# digital_host_for_ADS1216_main.net
KiCad netlist of a schematic drawn in Altium Designer
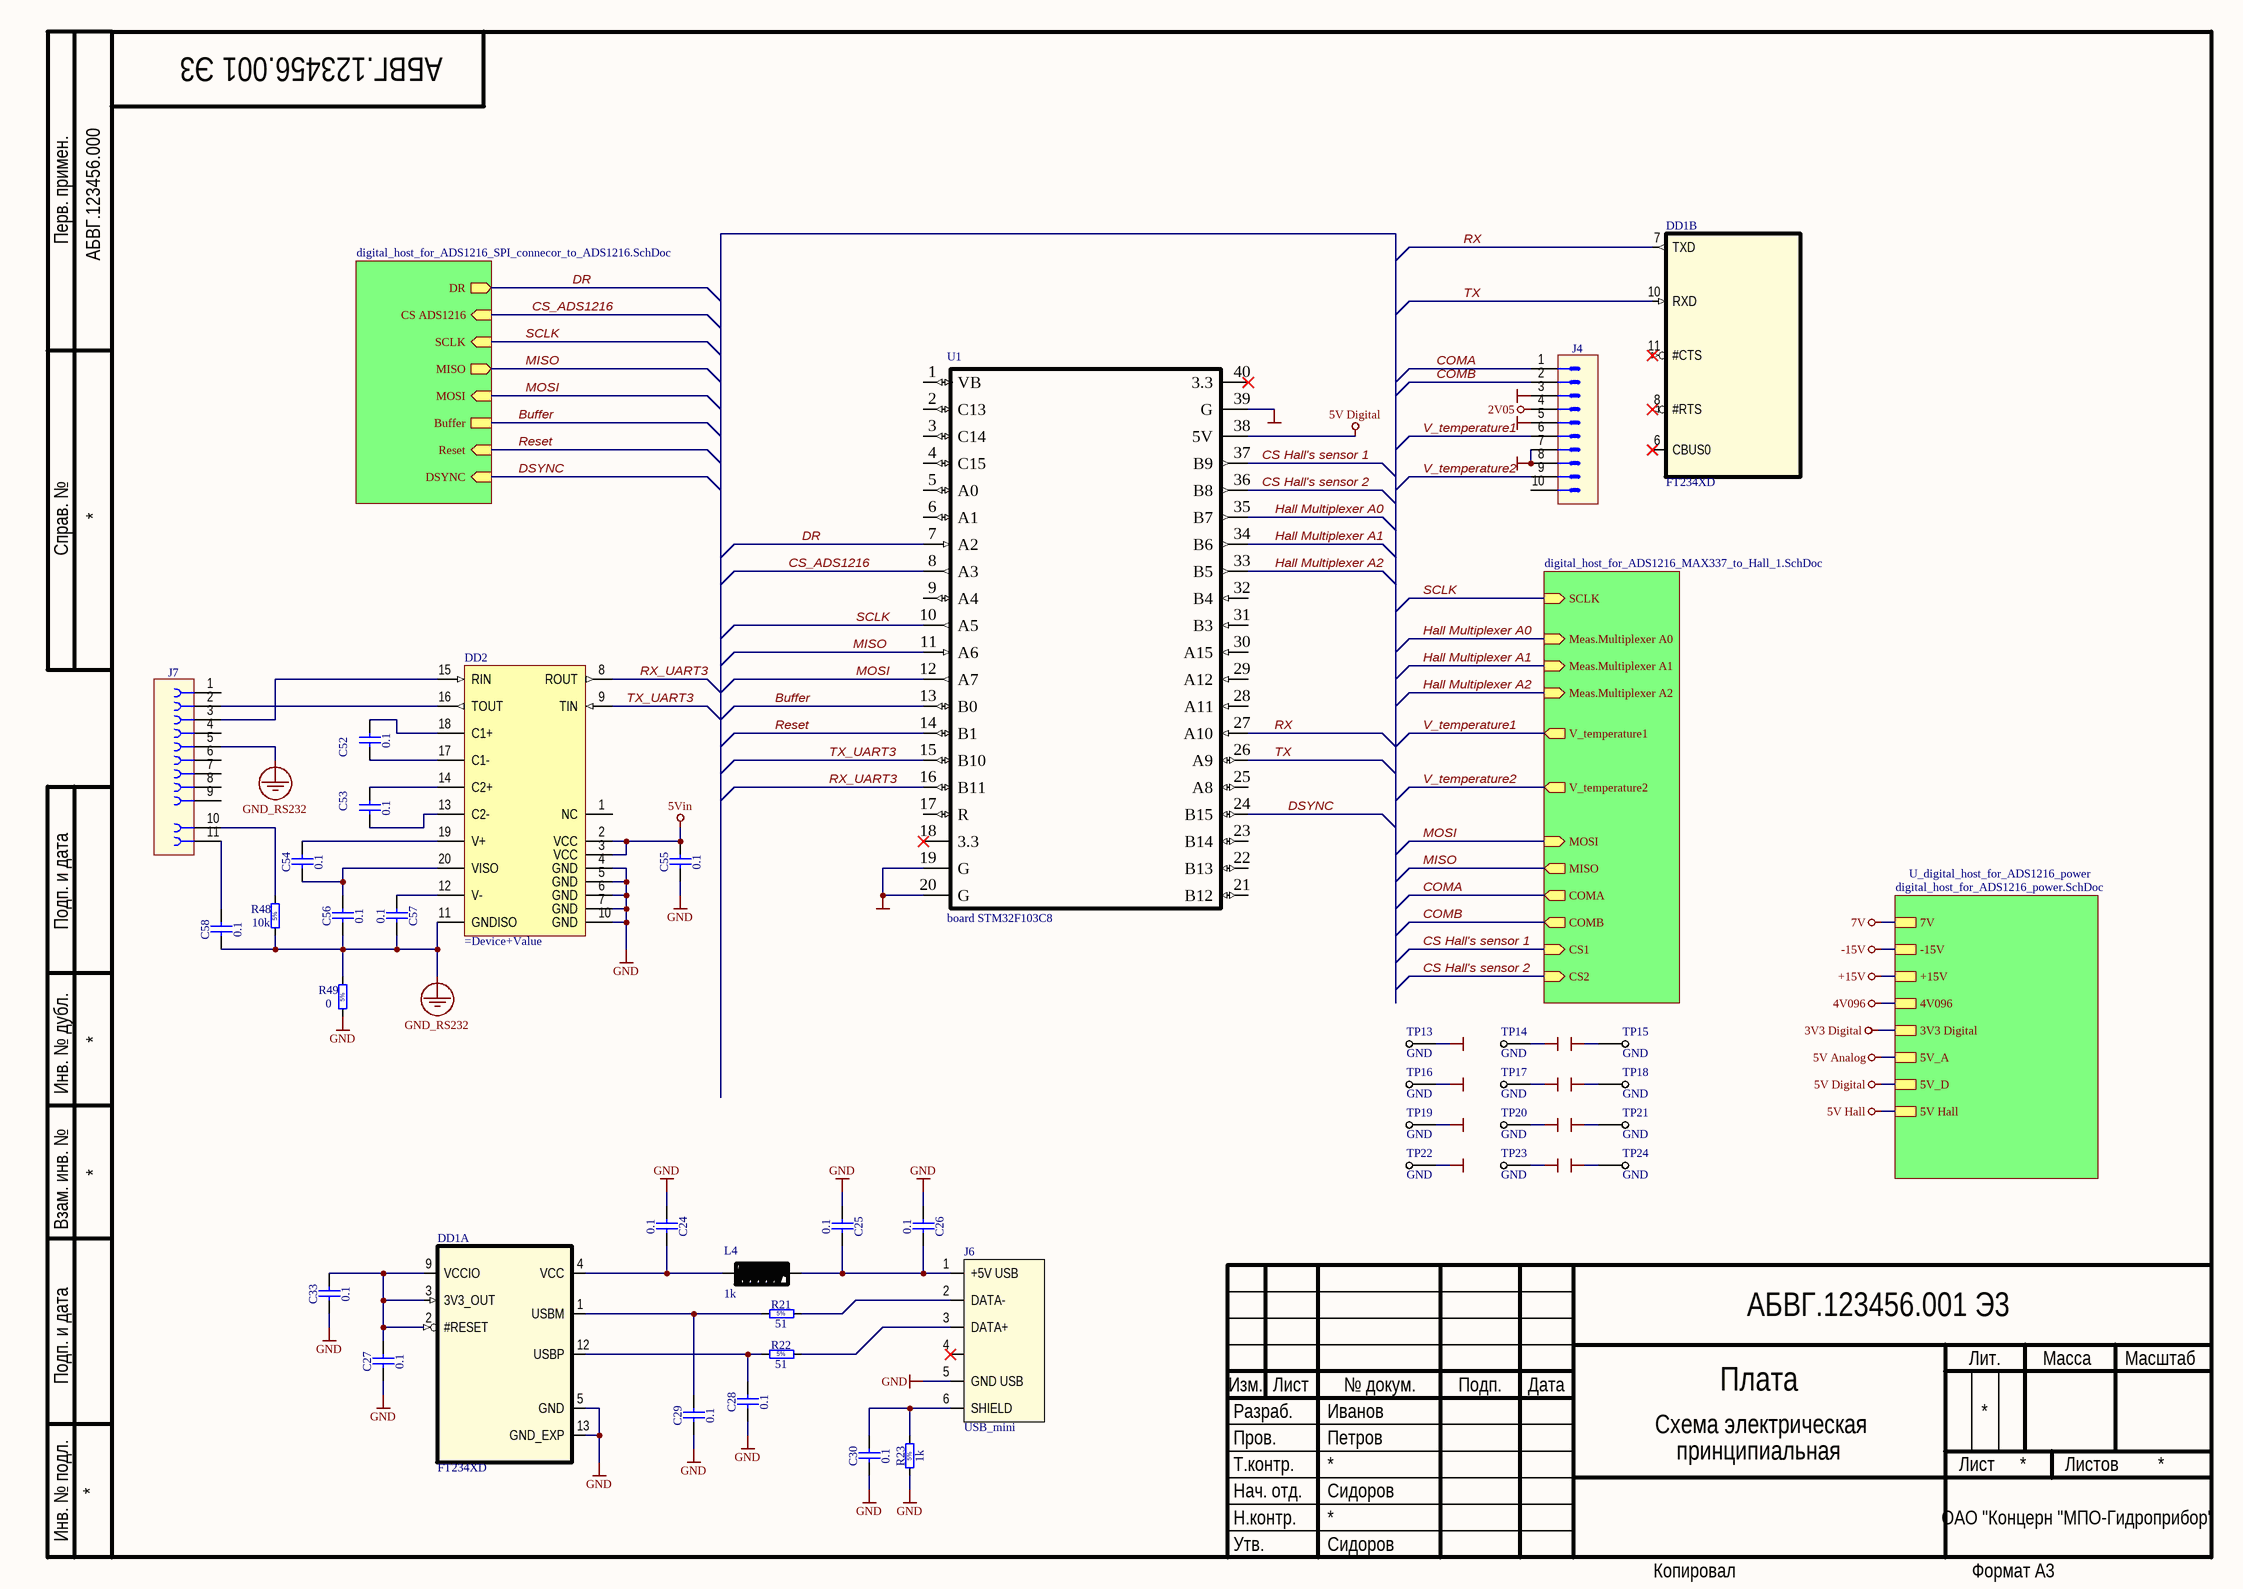
[diagram p0: digital_host_for_ADS1216_main.SchDoc]

(export (version "E")
  (design (tool "Eeschema 10.0.6"))
  (components
    (comp (ref "C24")
      (value "0.1")
      (footprint "CAPC2012X90N")
      (description "Non-polarised capacitor2012")
      (libsource (lib "schematic_hall_library") (part "Capacitor - non polarized"))
    )
    (comp (ref "C25")
      (value "0.1")
      (footprint "CAPC2012X90N")
      (description "Non-polarised capacitor2012")
      (libsource (lib "schematic_hall_library") (part "Capacitor - non polarized"))
    )
    (comp (ref "C26")
      (value "0.1")
      (footprint "CAPC2012X90N")
      (description "Non-polarised capacitor2012")
      (libsource (lib "schematic_hall_library") (part "Capacitor - non polarized"))
    )
    (comp (ref "C27")
      (value "0.1")
      (footprint "CAPC2012X90N")
      (description "Non-polarised capacitor2012")
      (libsource (lib "schematic_hall_library") (part "Capacitor - non polarized"))
    )
    (comp (ref "C28")
      (value "0.1")
      (footprint "CAPC2012X90N")
      (description "Non-polarised capacitor2012")
      (libsource (lib "schematic_hall_library") (part "Capacitor - non polarized"))
    )
    (comp (ref "C29")
      (value "0.1")
      (footprint "CAPC2012X90N")
      (description "Non-polarised capacitor2012")
      (libsource (lib "schematic_hall_library") (part "Capacitor - non polarized"))
    )
    (comp (ref "C30")
      (value "0.1")
      (footprint "CAPC2012X90N")
      (description "Non-polarised capacitor2012")
      (libsource (lib "schematic_hall_library") (part "Capacitor - non polarized"))
    )
    (comp (ref "C33")
      (value "0.1")
      (footprint "CAPC2012X90N")
      (description "Non-polarised capacitor2012")
      (libsource (lib "schematic_hall_library") (part "Capacitor - non polarized"))
    )
    (comp (ref "C52")
      (value "0.1")
      (footprint "CAPC2012X90N")
      (description "Non-polarised capacitor2012")
      (libsource (lib "schematic_hall_library") (part "Capacitor - non polarized"))
    )
    (comp (ref "C53")
      (value "0.1")
      (footprint "CAPC2012X90N")
      (description "Non-polarised capacitor2012")
      (libsource (lib "schematic_hall_library") (part "Capacitor - non polarized"))
    )
    (comp (ref "C54")
      (value "0.1")
      (footprint "CAPC2012X90N")
      (description "Non-polarised capacitor2012")
      (libsource (lib "schematic_hall_library") (part "Capacitor - non polarized"))
    )
    (comp (ref "C55")
      (value "0.1")
      (footprint "CAPC2012X90N")
      (description "Non-polarised capacitor2012")
      (libsource (lib "schematic_hall_library") (part "Capacitor - non polarized"))
    )
    (comp (ref "C56")
      (value "0.1")
      (footprint "CAPC2012X90N")
      (description "Non-polarised capacitor2012")
      (libsource (lib "schematic_hall_library") (part "Capacitor - non polarized"))
    )
    (comp (ref "C57")
      (value "0.1")
      (footprint "CAPC2012X90N")
      (description "Non-polarised capacitor2012")
      (libsource (lib "schematic_hall_library") (part "Capacitor - non polarized"))
    )
    (comp (ref "C58")
      (value "0.1")
      (footprint "CAPC2012X90N")
      (description "Non-polarised capacitor2012")
      (libsource (lib "schematic_hall_library") (part "Capacitor - non polarized"))
    )
    (comp (ref "DD1")
      (value "FT234XD")
      (footprint "DFN_12-045")
      (description "USB-UART driver")
      (libsource (lib "") (part "FT234XD_1"))
    )
    (comp (ref "DD2")
      (value "ADM3251")
      (footprint "footprint_hall_library:SOIC127P1032X265-20N")
      (description "Driver UART-RS232")
      (libsource (lib "schematic_hall_library") (part "ADM3251"))
    )
    (comp (ref "J4")
      (value "~")
      (footprint "footprint_library:3M_N2510-6002RB")
      (description "Connector 10 Male")
      (libsource (lib "first_scheme.~(65)") (part "Connector 10 Male"))
    )
    (comp (ref "J6")
      (value "USB_mini")
      (footprint "TYCO_1734035-1")
      (description "Вилка  PLS 6x2.54")
      (libsource (lib "Integrated_Library1") (part "USB_mini"))
    )
    (comp (ref "J7")
      (value "~")
      (footprint "footprint_hall_library:TYCO_5747844-5")
      (description "Connector 9 Female")
      (libsource (lib "schematic_hall_library") (part "Connector 9 Female"))
    )
    (comp (ref "L4")
      (value "1k")
      (footprint "footprint_library:RESC2012X50N")
      (description "SMD Ferrite bead 0805")
      (libsource (lib "first_scheme.~(65)") (part "BLM21"))
    )
    (comp (ref "R21")
      (value "51")
      (footprint "RESC2012X70N")
      (description "Resistor - 5%")
      (fields (field (name "TOLERANCE") "5%"))
      (libsource (lib "first_scheme.~(65)") (part "Resistor - 5%"))
    )
    (comp (ref "R22")
      (value "51")
      (footprint "RESC2012X70N")
      (description "Resistor - 5%")
      (fields (field (name "TOLERANCE") "5%"))
      (libsource (lib "first_scheme.~(65)") (part "Resistor - 5%"))
    )
    (comp (ref "R23")
      (value "1k")
      (footprint "RESC2012X70N")
      (description "Resistor - 5%")
      (fields (field (name "TOLERANCE") "5%"))
      (libsource (lib "first_scheme.~(65)") (part "Resistor - 5%"))
    )
    (comp (ref "R48")
      (value "10k")
      (footprint "RESC2012X70N")
      (description "Resistor - 5%")
      (fields (field (name "TOLERANCE") "5%"))
      (libsource (lib "first_scheme.~(65)") (part "Resistor - 5%"))
    )
    (comp (ref "R49")
      (value "0")
      (footprint "RESC2012X70N")
      (description "Resistor - 5%")
      (fields (field (name "TOLERANCE") "5%"))
      (libsource (lib "first_scheme.~(65)") (part "Resistor - 5%"))
    )
    (comp (ref "TP13")
      (value "GND")
      (footprint "TP1")
      (description "Контрольная точка")
      (libsource (lib "Integrated_Library1") (part "TP"))
    )
    (comp (ref "TP14")
      (value "GND")
      (footprint "TP1")
      (description "Контрольная точка")
      (libsource (lib "Integrated_Library1") (part "TP"))
    )
    (comp (ref "TP15")
      (value "GND")
      (footprint "TP1")
      (description "Контрольная точка")
      (libsource (lib "Integrated_Library1") (part "TP"))
    )
    (comp (ref "TP16")
      (value "GND")
      (footprint "TP1")
      (description "Контрольная точка")
      (libsource (lib "Integrated_Library1") (part "TP"))
    )
    (comp (ref "TP17")
      (value "GND")
      (footprint "TP1")
      (description "Контрольная точка")
      (libsource (lib "Integrated_Library1") (part "TP"))
    )
    (comp (ref "TP18")
      (value "GND")
      (footprint "TP1")
      (description "Контрольная точка")
      (libsource (lib "Integrated_Library1") (part "TP"))
    )
    (comp (ref "TP19")
      (value "GND")
      (footprint "TP1")
      (description "Контрольная точка")
      (libsource (lib "Integrated_Library1") (part "TP"))
    )
    (comp (ref "TP20")
      (value "GND")
      (footprint "TP1")
      (description "Контрольная точка")
      (libsource (lib "Integrated_Library1") (part "TP"))
    )
    (comp (ref "TP21")
      (value "GND")
      (footprint "TP1")
      (description "Контрольная точка")
      (libsource (lib "Integrated_Library1") (part "TP"))
    )
    (comp (ref "TP22")
      (value "GND")
      (footprint "TP1")
      (description "Контрольная точка")
      (libsource (lib "Integrated_Library1") (part "TP"))
    )
    (comp (ref "TP23")
      (value "GND")
      (footprint "TP1")
      (description "Контрольная точка")
      (libsource (lib "Integrated_Library1") (part "TP"))
    )
    (comp (ref "TP24")
      (value "GND")
      (footprint "TP1")
      (description "Контрольная точка")
      (libsource (lib "Integrated_Library1") (part "TP"))
    )
    (comp (ref "U1")
      (value "board STM32F103C8")
      (footprint "footprint_library:blue_pill")
      (description "Blue Pill board")
      (libsource (lib "first_scheme.~(65)") (part "Blue Pill"))
    )
  )
  (nets
    (net (code "3") (name "/Buffer") (class "Default")
      (node (ref "U1") (pin "13") (pinfunction "B0_13") (pintype "bidirectional"))
    )
    (net (code "4") (name "/COMA") (class "Default")
      (node (ref "J4") (pin "1") (pinfunction "1_1") (pintype "passive"))
    )
    (net (code "5") (name "/COMB") (class "Default")
      (node (ref "J4") (pin "2") (pinfunction "2_2") (pintype "passive"))
    )
    (net (code "6") (name "/CS Hall's sensor 1") (class "Default")
      (node (ref "U1") (pin "37") (pinfunction "B9_37") (pintype "output"))
    )
    (net (code "7") (name "/CS Hall's sensor 2") (class "Default")
      (node (ref "U1") (pin "36") (pinfunction "B8_36") (pintype "output"))
    )
    (net (code "8") (name "/CS_ADS1216") (class "Default")
      (node (ref "U1") (pin "8") (pinfunction "A3_8") (pintype "output"))
    )
    (net (code "9") (name "/DR") (class "Default")
      (node (ref "U1") (pin "7") (pinfunction "A2_7") (pintype "input"))
    )
    (net (code "10") (name "/DSYNC") (class "Default")
      (node (ref "U1") (pin "24") (pinfunction "B15_24") (pintype "bidirectional"))
    )
    (net (code "11") (name "/Hall Multiplexer A0") (class "Default")
      (node (ref "U1") (pin "35") (pinfunction "B7_35") (pintype "output"))
    )
    (net (code "12") (name "/Hall Multiplexer A1") (class "Default")
      (node (ref "U1") (pin "34") (pinfunction "B6_34") (pintype "output"))
    )
    (net (code "13") (name "/Hall Multiplexer A2") (class "Default")
      (node (ref "U1") (pin "33") (pinfunction "B5_33") (pintype "output"))
    )
    (net (code "14") (name "/MISO") (class "Default")
      (node (ref "U1") (pin "11") (pinfunction "A6_11") (pintype "input"))
    )
    (net (code "15") (name "/MOSI") (class "Default")
      (node (ref "U1") (pin "12") (pinfunction "A7_12") (pintype "output"))
    )
    (net (code "16") (name "/RX") (class "Default")
      (node (ref "DD1") (pin "7") (pinfunction "TXD_7") (pintype "output"))
      (node (ref "U1") (pin "27") (pinfunction "A10_27") (pintype "input"))
    )
    (net (code "17") (name "/RX_UART3") (class "Default")
      (node (ref "DD2") (pin "8") (pinfunction "ROUT_8") (pintype "output"))
      (node (ref "U1") (pin "16") (pinfunction "B11_16") (pintype "bidirectional"))
    )
    (net (code "18") (name "/Reset") (class "Default")
      (node (ref "U1") (pin "14") (pinfunction "B1_14") (pintype "bidirectional"))
    )
    (net (code "19") (name "/SCLK") (class "Default")
      (node (ref "U1") (pin "10") (pinfunction "A5_10") (pintype "output"))
    )
    (net (code "20") (name "/TX") (class "Default")
      (node (ref "DD1") (pin "10") (pinfunction "RXD_10") (pintype "input"))
      (node (ref "U1") (pin "26") (pinfunction "A9_26") (pintype "bidirectional"))
    )
    (net (code "21") (name "/TX_UART3") (class "Default")
      (node (ref "DD2") (pin "9") (pinfunction "TIN_9") (pintype "input"))
      (node (ref "U1") (pin "15") (pinfunction "B10_15") (pintype "bidirectional"))
    )
    (net (code "22") (name "/V_temperature1") (class "Default")
      (node (ref "J4") (pin "6") (pinfunction "6_6") (pintype "passive"))
    )
    (net (code "23") (name "/V_temperature2") (class "Default")
      (node (ref "J4") (pin "9") (pinfunction "9_9") (pintype "passive"))
    )
    (net (code "24") (name "2V05") (class "Default")
      (node (ref "J4") (pin "4") (pinfunction "4_4") (pintype "passive"))
    )
    (net (code "28") (name "5V Digital") (class "Default")
      (node (ref "U1") (pin "38") (pinfunction "5V_38") (pintype "power_in"))
    )
    (net (code "30") (name "5Vin") (class "Default")
      (node (ref "C55") (pin "1") (pinfunction "1_1") (pintype "passive"))
      (node (ref "DD2") (pin "2") (pinfunction "VCC_2") (pintype "power_in"))
      (node (ref "DD2") (pin "3") (pinfunction "VCC_3") (pintype "power_in"))
    )
    (net (code "32") (name "GND") (class "Default")
      (node (ref "C24") (pin "1") (pinfunction "1_1") (pintype "passive"))
      (node (ref "C25") (pin "1") (pinfunction "1_1") (pintype "passive"))
      (node (ref "C26") (pin "1") (pinfunction "1_1") (pintype "passive"))
      (node (ref "C27") (pin "1") (pinfunction "1_1") (pintype "passive"))
      (node (ref "C28") (pin "1") (pinfunction "1_1") (pintype "passive"))
      (node (ref "C29") (pin "1") (pinfunction "1_1") (pintype "passive"))
      (node (ref "C30") (pin "1") (pinfunction "1_1") (pintype "passive"))
      (node (ref "C33") (pin "1") (pinfunction "1_1") (pintype "passive"))
      (node (ref "C55") (pin "2") (pinfunction "2_2") (pintype "passive"))
      (node (ref "DD1") (pin "13") (pinfunction "GND_EXP_13") (pintype "power_in"))
      (node (ref "DD1") (pin "5") (pinfunction "GND_5") (pintype "power_in"))
      (node (ref "DD2") (pin "10") (pinfunction "GND_10") (pintype "power_in"))
      (node (ref "DD2") (pin "4") (pinfunction "GND_4") (pintype "power_in"))
      (node (ref "DD2") (pin "5") (pinfunction "GND_5") (pintype "power_in"))
      (node (ref "DD2") (pin "6") (pinfunction "GND_6") (pintype "power_in"))
      (node (ref "DD2") (pin "7") (pinfunction "GND_7") (pintype "power_in"))
      (node (ref "J4") (pin "3") (pinfunction "3_3") (pintype "passive"))
      (node (ref "J4") (pin "5") (pinfunction "5_5") (pintype "passive"))
      (node (ref "J4") (pin "7") (pinfunction "7_7") (pintype "passive"))
      (node (ref "J4") (pin "8") (pinfunction "8_8") (pintype "passive"))
      (node (ref "J6") (pin "5") (pinfunction "GND_USB_5") (pintype "passive"))
      (node (ref "R23") (pin "1") (pinfunction "1_1") (pintype "passive"))
      (node (ref "R49") (pin "1") (pinfunction "1_1") (pintype "passive"))
      (node (ref "TP13") (pin "1") (pinfunction "P_1") (pintype "passive"))
      (node (ref "TP14") (pin "1") (pinfunction "P_1") (pintype "passive"))
      (node (ref "TP15") (pin "1") (pinfunction "P_1") (pintype "passive"))
      (node (ref "TP16") (pin "1") (pinfunction "P_1") (pintype "passive"))
      (node (ref "TP17") (pin "1") (pinfunction "P_1") (pintype "passive"))
      (node (ref "TP18") (pin "1") (pinfunction "P_1") (pintype "passive"))
      (node (ref "TP19") (pin "1") (pinfunction "P_1") (pintype "passive"))
      (node (ref "TP20") (pin "1") (pinfunction "P_1") (pintype "passive"))
      (node (ref "TP21") (pin "1") (pinfunction "P_1") (pintype "passive"))
      (node (ref "TP22") (pin "1") (pinfunction "P_1") (pintype "passive"))
      (node (ref "TP23") (pin "1") (pinfunction "P_1") (pintype "passive"))
      (node (ref "TP24") (pin "1") (pinfunction "P_1") (pintype "passive"))
      (node (ref "U1") (pin "19") (pinfunction "G_19") (pintype "power_in"))
      (node (ref "U1") (pin "20") (pinfunction "G_20") (pintype "power_in"))
      (node (ref "U1") (pin "39") (pinfunction "G_39") (pintype "power_in"))
    )
    (net (code "33") (name "GND_RS232") (class "Default")
      (node (ref "C56") (pin "2") (pinfunction "2_2") (pintype "passive"))
      (node (ref "C57") (pin "1") (pinfunction "1_1") (pintype "passive"))
      (node (ref "C58") (pin "2") (pinfunction "2_2") (pintype "passive"))
      (node (ref "DD2") (pin "11") (pinfunction "GNDISO_11") (pintype "power_in"))
      (node (ref "J7") (pin "5") (pinfunction "5_5") (pintype "passive"))
      (node (ref "R48") (pin "1") (pinfunction "1_1") (pintype "passive"))
      (node (ref "R49") (pin "2") (pinfunction "2_2") (pintype "passive"))
    )
    (net (code "34") (name "Net-(C58-Pad1)") (class "Default")
      (node (ref "C58") (pin "1") (pinfunction "1_1") (pintype "passive"))
      (node (ref "J7") (pin "11") (pinfunction "11_11") (pintype "passive"))
    )
    (net (code "35") (name "Net-(DD1A-#RESET)") (class "Default")
      (node (ref "C27") (pin "2") (pinfunction "2_2") (pintype "passive"))
      (node (ref "C33") (pin "2") (pinfunction "2_2") (pintype "passive"))
      (node (ref "DD1") (pin "2") (pinfunction "#RESET_2") (pintype "input"))
      (node (ref "DD1") (pin "3") (pinfunction "3V3_OUT_3") (pintype "input"))
      (node (ref "DD1") (pin "9") (pinfunction "VCCIO_9") (pintype "power_in"))
    )
    (net (code "36") (name "Net-(DD1A-USBM)") (class "Default")
      (node (ref "C29") (pin "2") (pinfunction "2_2") (pintype "passive"))
      (node (ref "DD1") (pin "1") (pinfunction "USBM_1") (pintype "bidirectional"))
      (node (ref "R21") (pin "1") (pinfunction "1_1") (pintype "passive"))
    )
    (net (code "37") (name "Net-(DD1A-USBP)") (class "Default")
      (node (ref "C28") (pin "2") (pinfunction "2_2") (pintype "passive"))
      (node (ref "DD1") (pin "12") (pinfunction "USBP_12") (pintype "bidirectional"))
      (node (ref "R22") (pin "1") (pinfunction "1_1") (pintype "passive"))
    )
    (net (code "38") (name "Net-(DD1A-VCC)") (class "Default")
      (node (ref "C24") (pin "2") (pinfunction "2_2") (pintype "passive"))
      (node (ref "DD1") (pin "4") (pinfunction "VCC_4") (pintype "power_in"))
      (node (ref "L4") (pin "1") (pinfunction "1_1") (pintype "passive"))
    )
    (net (code "39") (name "Net-(DD2-C1+)") (class "Default")
      (node (ref "C52") (pin "1") (pinfunction "1_1") (pintype "passive"))
      (node (ref "DD2") (pin "18") (pinfunction "C1+_18") (pintype "passive"))
    )
    (net (code "40") (name "Net-(DD2-C1-)") (class "Default")
      (node (ref "C52") (pin "2") (pinfunction "2_2") (pintype "passive"))
      (node (ref "DD2") (pin "17") (pinfunction "C1-_17") (pintype "passive"))
    )
    (net (code "41") (name "Net-(DD2-C2+)") (class "Default")
      (node (ref "C53") (pin "1") (pinfunction "1_1") (pintype "passive"))
      (node (ref "DD2") (pin "14") (pinfunction "C2+_14") (pintype "passive"))
    )
    (net (code "42") (name "Net-(DD2-C2-)") (class "Default")
      (node (ref "C53") (pin "2") (pinfunction "2_2") (pintype "passive"))
      (node (ref "DD2") (pin "13") (pinfunction "C2-_13") (pintype "passive"))
    )
    (net (code "43") (name "Net-(DD2-RIN)") (class "Default")
      (node (ref "DD2") (pin "15") (pinfunction "RIN_15") (pintype "input"))
      (node (ref "J7") (pin "3") (pinfunction "3_3") (pintype "passive"))
    )
    (net (code "44") (name "Net-(DD2-TOUT)") (class "Default")
      (node (ref "DD2") (pin "16") (pinfunction "TOUT_16") (pintype "output"))
      (node (ref "J7") (pin "2") (pinfunction "2_2") (pintype "passive"))
    )
    (net (code "45") (name "Net-(DD2-V+)") (class "Default")
      (node (ref "C54") (pin "1") (pinfunction "1_1") (pintype "passive"))
      (node (ref "DD2") (pin "19") (pinfunction "V+_19") (pintype "power_in"))
    )
    (net (code "46") (name "Net-(DD2-V-)") (class "Default")
      (node (ref "C57") (pin "2") (pinfunction "2_2") (pintype "passive"))
      (node (ref "DD2") (pin "12") (pinfunction "V-_12") (pintype "power_in"))
    )
    (net (code "47") (name "Net-(DD2-VISO)") (class "Default")
      (node (ref "C54") (pin "2") (pinfunction "2_2") (pintype "passive"))
      (node (ref "C56") (pin "1") (pinfunction "1_1") (pintype "passive"))
      (node (ref "DD2") (pin "20") (pinfunction "VISO_20") (pintype "power_in"))
    )
    (net (code "48") (name "Net-(J6-+5V_USB)") (class "Default")
      (node (ref "C25") (pin "2") (pinfunction "2_2") (pintype "passive"))
      (node (ref "C26") (pin "2") (pinfunction "2_2") (pintype "passive"))
      (node (ref "J6") (pin "1") (pinfunction "+5V_USB_1") (pintype "passive"))
      (node (ref "L4") (pin "2") (pinfunction "2_2") (pintype "passive"))
    )
    (net (code "49") (name "Net-(J6-DATA+)") (class "Default")
      (node (ref "J6") (pin "3") (pinfunction "DATA+_3") (pintype "passive"))
      (node (ref "R22") (pin "2") (pinfunction "2_2") (pintype "passive"))
    )
    (net (code "50") (name "Net-(J6-DATA-)") (class "Default")
      (node (ref "J6") (pin "2") (pinfunction "DATA-_2") (pintype "passive"))
      (node (ref "R21") (pin "2") (pinfunction "2_2") (pintype "passive"))
    )
    (net (code "51") (name "Net-(J6-SHIELD)") (class "Default")
      (node (ref "C30") (pin "2") (pinfunction "2_2") (pintype "passive"))
      (node (ref "J6") (pin "6") (pinfunction "SHIELD_6") (pintype "passive"))
      (node (ref "R23") (pin "2") (pinfunction "2_2") (pintype "passive"))
    )
    (net (code "52") (name "Net-(J7-Pad10)") (class "Default")
      (node (ref "J7") (pin "10") (pinfunction "10_10") (pintype "passive"))
      (node (ref "R48") (pin "2") (pinfunction "2_2") (pintype "passive"))
    )
    (net (code "53") (name "unconnected-(DD1B-#CTS-Pad11)") (class "Default")
      (node (ref "DD1") (pin "11") (pinfunction "#CTS_11") (pintype "input+no_connect"))
    )
    (net (code "54") (name "unconnected-(DD1B-#RTS-Pad8)") (class "Default")
      (node (ref "DD1") (pin "8") (pinfunction "#RTS_8") (pintype "output+no_connect"))
    )
    (net (code "55") (name "unconnected-(DD1B-CBUS0-Pad6)") (class "Default")
      (node (ref "DD1") (pin "6") (pinfunction "CBUS0_6") (pintype "bidirectional+no_connect"))
    )
    (net (code "56") (name "unconnected-(DD2-NC-Pad1)") (class "Default")
      (node (ref "DD2") (pin "1") (pinfunction "NC_1") (pintype "passive"))
    )
    (net (code "57") (name "unconnected-(J4-Pad10)") (class "Default")
      (node (ref "J4") (pin "10") (pinfunction "10_10") (pintype "passive"))
    )
    (net (code "58") (name "unconnected-(J6-Pad4)") (class "Default")
      (node (ref "J6") (pin "4") (pinfunction "4_4") (pintype "passive+no_connect"))
    )
    (net (code "59") (name "unconnected-(J7-Pad1)") (class "Default")
      (node (ref "J7") (pin "1") (pinfunction "1_1") (pintype "passive"))
    )
    (net (code "60") (name "unconnected-(J7-Pad4)") (class "Default")
      (node (ref "J7") (pin "4") (pinfunction "4_4") (pintype "passive"))
    )
    (net (code "61") (name "unconnected-(J7-Pad6)") (class "Default")
      (node (ref "J7") (pin "6") (pinfunction "6_6") (pintype "passive"))
    )
    (net (code "62") (name "unconnected-(J7-Pad7)") (class "Default")
      (node (ref "J7") (pin "7") (pinfunction "7_7") (pintype "passive"))
    )
    (net (code "63") (name "unconnected-(J7-Pad8)") (class "Default")
      (node (ref "J7") (pin "8") (pinfunction "8_8") (pintype "passive"))
    )
    (net (code "64") (name "unconnected-(J7-Pad9)") (class "Default")
      (node (ref "J7") (pin "9") (pinfunction "9_9") (pintype "passive"))
    )
    (net (code "65") (name "unconnected-(U1-3.3-Pad18)") (class "Default")
      (node (ref "U1") (pin "18") (pinfunction "3.3_18") (pintype "power_in+no_connect"))
    )
    (net (code "66") (name "unconnected-(U1-3.3-Pad40)") (class "Default")
      (node (ref "U1") (pin "40") (pinfunction "3.3_40") (pintype "power_in+no_connect"))
    )
    (net (code "67") (name "unconnected-(U1-A0-Pad5)") (class "Default")
      (node (ref "U1") (pin "5") (pinfunction "A0_5") (pintype "bidirectional"))
    )
    (net (code "68") (name "unconnected-(U1-A1-Pad6)") (class "Default")
      (node (ref "U1") (pin "6") (pinfunction "A1_6") (pintype "bidirectional"))
    )
    (net (code "69") (name "unconnected-(U1-A4-Pad9)") (class "Default")
      (node (ref "U1") (pin "9") (pinfunction "A4_9") (pintype "bidirectional"))
    )
    (net (code "70") (name "unconnected-(U1-A8-Pad25)") (class "Default")
      (node (ref "U1") (pin "25") (pinfunction "A8_25") (pintype "bidirectional"))
    )
    (net (code "71") (name "unconnected-(U1-A11-Pad28)") (class "Default")
      (node (ref "U1") (pin "28") (pinfunction "A11_28") (pintype "input"))
    )
    (net (code "72") (name "unconnected-(U1-A12-Pad29)") (class "Default")
      (node (ref "U1") (pin "29") (pinfunction "A12_29") (pintype "input"))
    )
    (net (code "73") (name "unconnected-(U1-A15-Pad30)") (class "Default")
      (node (ref "U1") (pin "30") (pinfunction "A15_30") (pintype "input"))
    )
    (net (code "74") (name "unconnected-(U1-B3-Pad31)") (class "Default")
      (node (ref "U1") (pin "31") (pinfunction "B3_31") (pintype "input"))
    )
    (net (code "75") (name "unconnected-(U1-B4-Pad32)") (class "Default")
      (node (ref "U1") (pin "32") (pinfunction "B4_32") (pintype "input"))
    )
    (net (code "76") (name "unconnected-(U1-B12-Pad21)") (class "Default")
      (node (ref "U1") (pin "21") (pinfunction "B12_21") (pintype "bidirectional"))
    )
    (net (code "77") (name "unconnected-(U1-B13-Pad22)") (class "Default")
      (node (ref "U1") (pin "22") (pinfunction "B13_22") (pintype "bidirectional"))
    )
    (net (code "78") (name "unconnected-(U1-B14-Pad23)") (class "Default")
      (node (ref "U1") (pin "23") (pinfunction "B14_23") (pintype "bidirectional"))
    )
    (net (code "79") (name "unconnected-(U1-C13-Pad2)") (class "Default")
      (node (ref "U1") (pin "2") (pinfunction "C13_2") (pintype "bidirectional"))
    )
    (net (code "80") (name "unconnected-(U1-C14-Pad3)") (class "Default")
      (node (ref "U1") (pin "3") (pinfunction "C14_3") (pintype "bidirectional"))
    )
    (net (code "81") (name "unconnected-(U1-C15-Pad4)") (class "Default")
      (node (ref "U1") (pin "4") (pinfunction "C15_4") (pintype "bidirectional"))
    )
    (net (code "82") (name "unconnected-(U1-R-Pad17)") (class "Default")
      (node (ref "U1") (pin "17") (pinfunction "R_17") (pintype "bidirectional"))
    )
    (net (code "83") (name "unconnected-(U1-VB-Pad1)") (class "Default")
      (node (ref "U1") (pin "1") (pinfunction "VB_1") (pintype "bidirectional"))
    )
  )
)
